# 36.net
KiCad netlist of a schematic drawn in Altium Designer
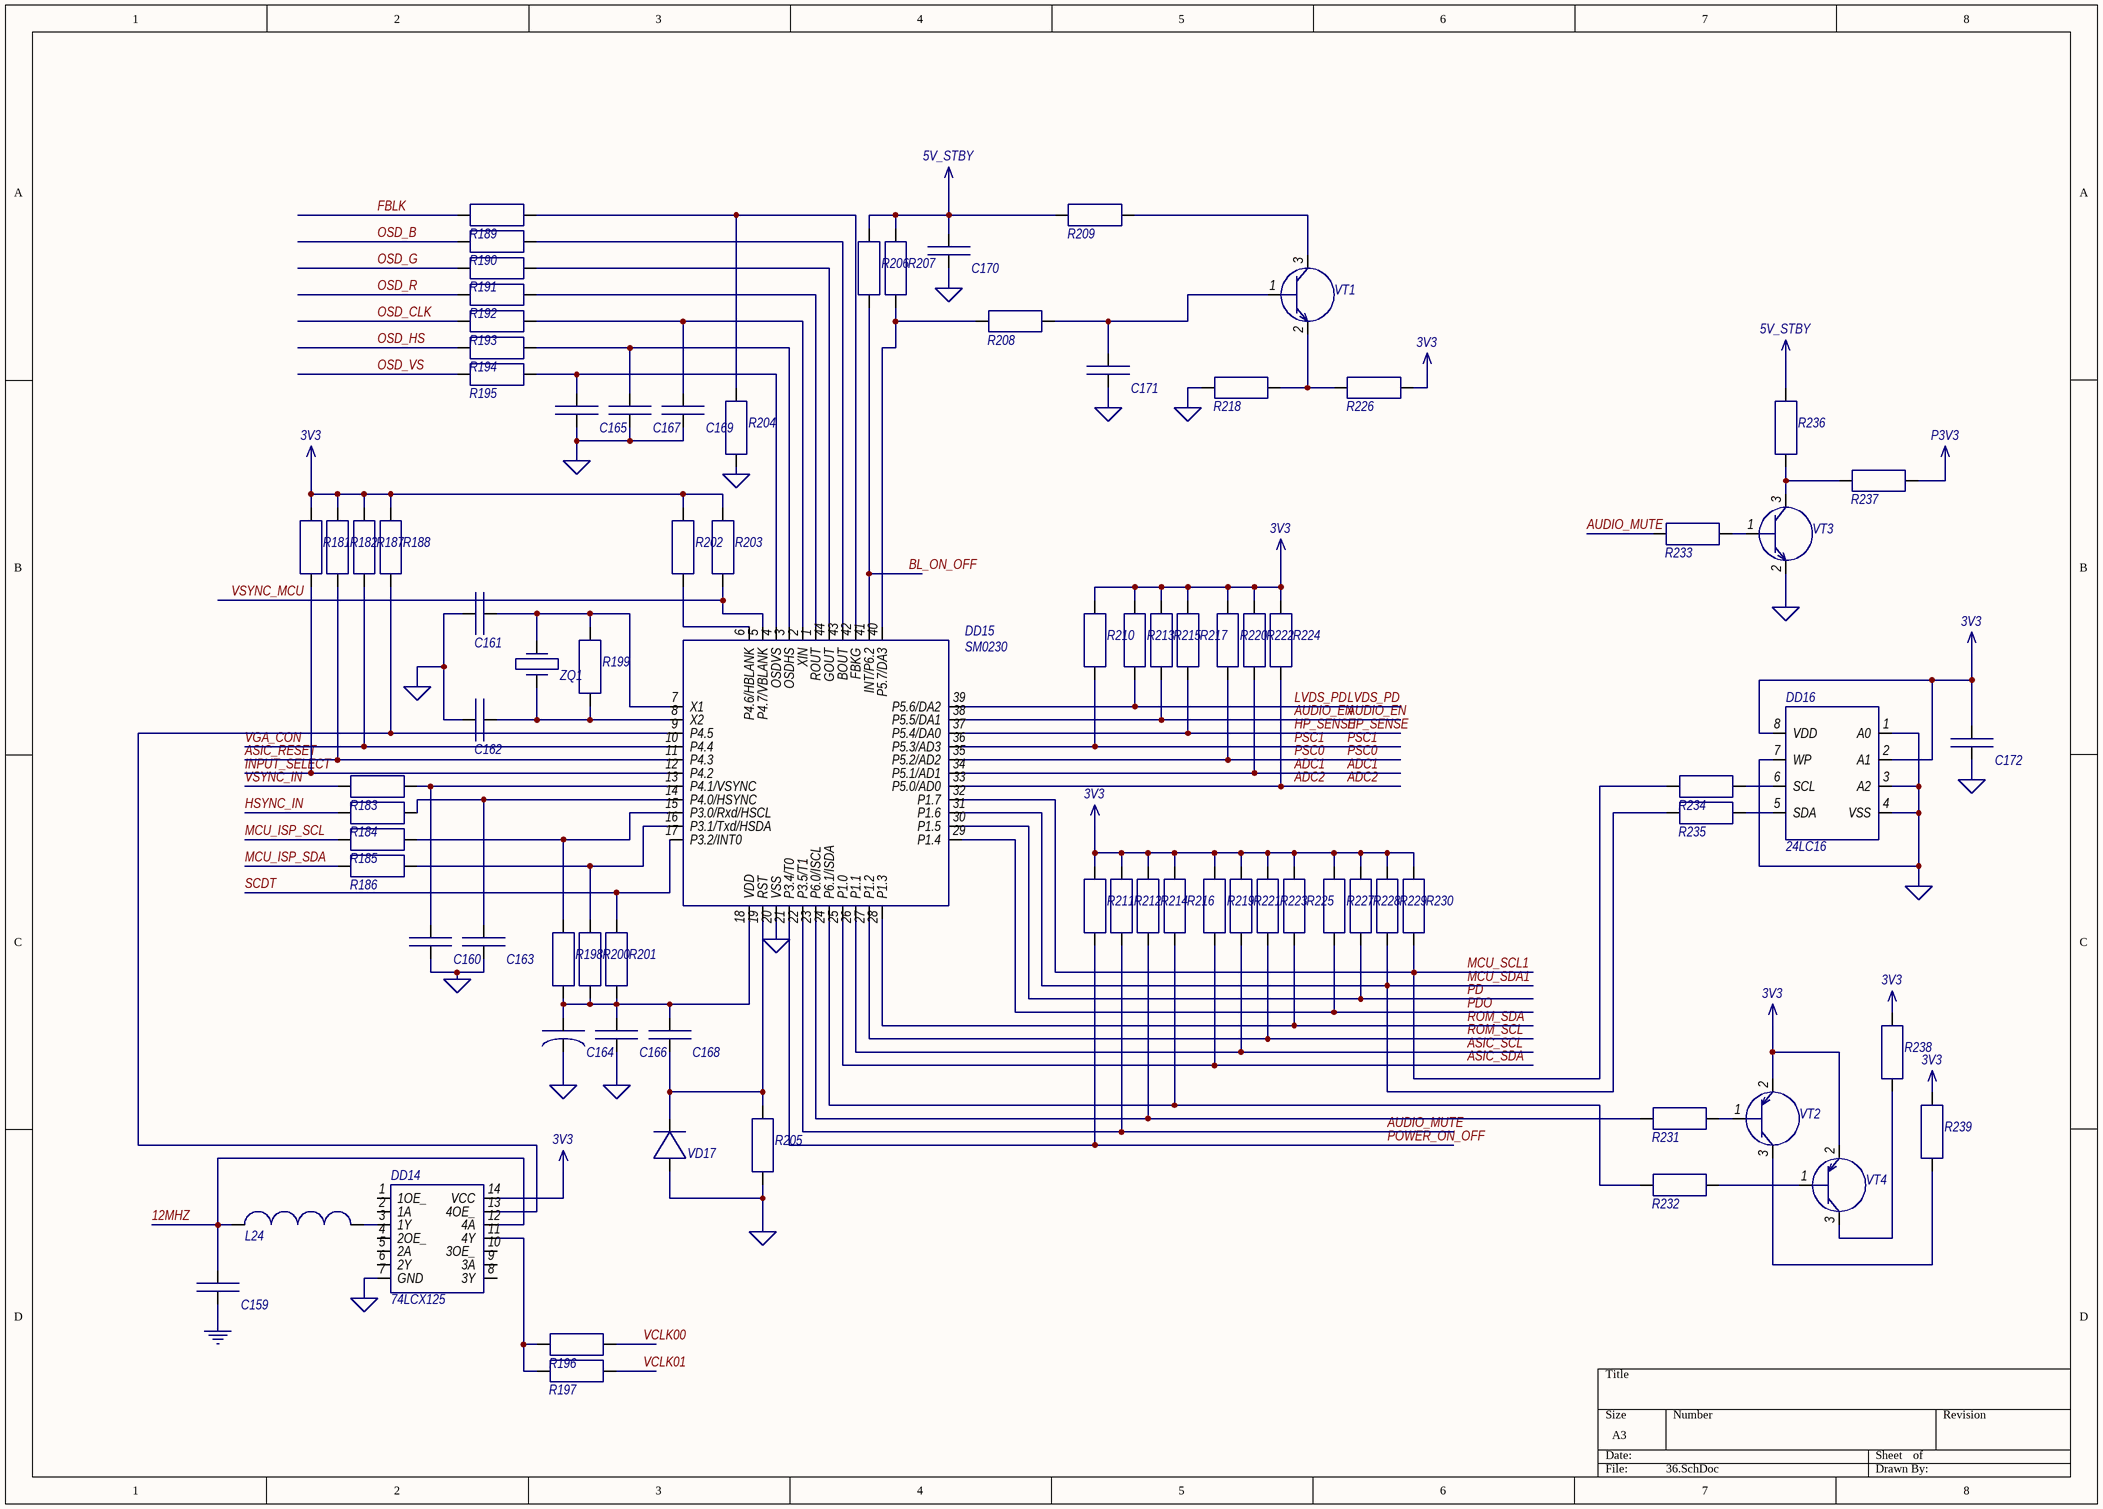
[diagram p0: 36.SchDoc]

(export (version "E")
  (design (tool "Eeschema 10.0.6"))
  (components
    (comp (ref "C159")
      (value "Capacitor")
      (footprint "cap_electro_13")
      (libsource (lib "31_lib") (part "Capacitor"))
    )
    (comp (ref "C160")
      (value "Capacitor")
      (footprint "cap_electro_13")
      (libsource (lib "31_lib") (part "Capacitor"))
    )
    (comp (ref "C161")
      (value "Capacitor")
      (footprint "cap_electro_13")
      (libsource (lib "31_lib") (part "Capacitor"))
    )
    (comp (ref "C162")
      (value "Capacitor")
      (footprint "cap_electro_13")
      (libsource (lib "31_lib") (part "Capacitor"))
    )
    (comp (ref "C163")
      (value "Capacitor")
      (footprint "cap_electro_13")
      (libsource (lib "31_lib") (part "Capacitor"))
    )
    (comp (ref "C164")
      (value "TuningCapacitor")
      (footprint "31_lib:Cap_tantal_D")
      (libsource (lib "31_lib") (part "TuningCapacitor"))
    )
    (comp (ref "C165")
      (value "Capacitor")
      (footprint "cap_electro_13")
      (libsource (lib "31_lib") (part "Capacitor"))
    )
    (comp (ref "C166")
      (value "Capacitor")
      (footprint "cap_electro_13")
      (libsource (lib "31_lib") (part "Capacitor"))
    )
    (comp (ref "C167")
      (value "Capacitor")
      (footprint "cap_electro_13")
      (libsource (lib "31_lib") (part "Capacitor"))
    )
    (comp (ref "C168")
      (value "Capacitor")
      (footprint "cap_electro_13")
      (libsource (lib "31_lib") (part "Capacitor"))
    )
    (comp (ref "C169")
      (value "Capacitor")
      (footprint "cap_electro_13")
      (libsource (lib "31_lib") (part "Capacitor"))
    )
    (comp (ref "C170")
      (value "Capacitor")
      (footprint "cap_electro_13")
      (libsource (lib "31_lib") (part "Capacitor"))
    )
    (comp (ref "C171")
      (value "Capacitor")
      (footprint "cap_electro_13")
      (libsource (lib "31_lib") (part "Capacitor"))
    )
    (comp (ref "C172")
      (value "Capacitor")
      (footprint "cap_electro_13")
      (libsource (lib "31_lib") (part "Capacitor"))
    )
    (comp (ref "DD14")
      (value "74LCX125")
      (footprint "31_lib:74LCX125(page12)")
      (libsource (lib "31_lib") (part "74LCX125"))
    )
    (comp (ref "DD15")
      (value "SM0230")
      (footprint "31_lib:SM0230")
      (libsource (lib "31_lib") (part "SM0230"))
    )
    (comp (ref "DD16") (value "24LC16") (footprint "31_lib:24Cxx") (libsource (lib "31_lib") (part "24LC16")))
    (comp (ref "L24")
      (value "Inductor")
      (footprint "31_lib:inductor")
      (libsource (lib "31_lib") (part "Inductor"))
    )
    (comp (ref "R181")
      (value "Resistor")
      (footprint "lab_7_footprints:R_1206")
      (libsource (lib "31_lib") (part "Resistor"))
    )
    (comp (ref "R182")
      (value "Resistor")
      (footprint "lab_7_footprints:R_1206")
      (libsource (lib "31_lib") (part "Resistor"))
    )
    (comp (ref "R183")
      (value "Resistor")
      (footprint "lab_7_footprints:R_1206")
      (libsource (lib "31_lib") (part "Resistor"))
    )
    (comp (ref "R184")
      (value "Resistor")
      (footprint "lab_7_footprints:R_1206")
      (libsource (lib "31_lib") (part "Resistor"))
    )
    (comp (ref "R185")
      (value "Resistor")
      (footprint "lab_7_footprints:R_1206")
      (libsource (lib "31_lib") (part "Resistor"))
    )
    (comp (ref "R186")
      (value "Resistor")
      (footprint "lab_7_footprints:R_1206")
      (libsource (lib "31_lib") (part "Resistor"))
    )
    (comp (ref "R187")
      (value "Resistor")
      (footprint "lab_7_footprints:R_1206")
      (libsource (lib "31_lib") (part "Resistor"))
    )
    (comp (ref "R188")
      (value "Resistor")
      (footprint "lab_7_footprints:R_1206")
      (libsource (lib "31_lib") (part "Resistor"))
    )
    (comp (ref "R189")
      (value "Resistor")
      (footprint "lab_7_footprints:R_1206")
      (libsource (lib "31_lib") (part "Resistor"))
    )
    (comp (ref "R190")
      (value "Resistor")
      (footprint "lab_7_footprints:R_1206")
      (libsource (lib "31_lib") (part "Resistor"))
    )
    (comp (ref "R191")
      (value "Resistor")
      (footprint "lab_7_footprints:R_1206")
      (libsource (lib "31_lib") (part "Resistor"))
    )
    (comp (ref "R192")
      (value "Resistor")
      (footprint "lab_7_footprints:R_1206")
      (libsource (lib "31_lib") (part "Resistor"))
    )
    (comp (ref "R193")
      (value "Resistor")
      (footprint "lab_7_footprints:R_1206")
      (libsource (lib "31_lib") (part "Resistor"))
    )
    (comp (ref "R194")
      (value "Resistor")
      (footprint "lab_7_footprints:R_1206")
      (libsource (lib "31_lib") (part "Resistor"))
    )
    (comp (ref "R195")
      (value "Resistor")
      (footprint "lab_7_footprints:R_1206")
      (libsource (lib "31_lib") (part "Resistor"))
    )
    (comp (ref "R196")
      (value "Resistor")
      (footprint "lab_7_footprints:R_1206")
      (libsource (lib "31_lib") (part "Resistor"))
    )
    (comp (ref "R197")
      (value "Resistor")
      (footprint "lab_7_footprints:R_1206")
      (libsource (lib "31_lib") (part "Resistor"))
    )
    (comp (ref "R198")
      (value "Resistor")
      (footprint "lab_7_footprints:R_1206")
      (libsource (lib "31_lib") (part "Resistor"))
    )
    (comp (ref "R199")
      (value "Resistor")
      (footprint "lab_7_footprints:R_1206")
      (libsource (lib "31_lib") (part "Resistor"))
    )
    (comp (ref "R200")
      (value "Resistor")
      (footprint "lab_7_footprints:R_1206")
      (libsource (lib "31_lib") (part "Resistor"))
    )
    (comp (ref "R201")
      (value "Resistor")
      (footprint "lab_7_footprints:R_1206")
      (libsource (lib "31_lib") (part "Resistor"))
    )
    (comp (ref "R202")
      (value "Resistor")
      (footprint "lab_7_footprints:R_1206")
      (libsource (lib "31_lib") (part "Resistor"))
    )
    (comp (ref "R203")
      (value "Resistor")
      (footprint "lab_7_footprints:R_1206")
      (libsource (lib "31_lib") (part "Resistor"))
    )
    (comp (ref "R204")
      (value "Resistor")
      (footprint "lab_7_footprints:R_1206")
      (libsource (lib "31_lib") (part "Resistor"))
    )
    (comp (ref "R205")
      (value "Resistor")
      (footprint "lab_7_footprints:R_1206")
      (libsource (lib "31_lib") (part "Resistor"))
    )
    (comp (ref "R206")
      (value "Resistor")
      (footprint "lab_7_footprints:R_1206")
      (libsource (lib "31_lib") (part "Resistor"))
    )
    (comp (ref "R207")
      (value "Resistor")
      (footprint "lab_7_footprints:R_1206")
      (libsource (lib "31_lib") (part "Resistor"))
    )
    (comp (ref "R208")
      (value "Resistor")
      (footprint "lab_7_footprints:R_1206")
      (libsource (lib "31_lib") (part "Resistor"))
    )
    (comp (ref "R209")
      (value "Resistor")
      (footprint "lab_7_footprints:R_1206")
      (libsource (lib "31_lib") (part "Resistor"))
    )
    (comp (ref "R210")
      (value "Resistor")
      (footprint "lab_7_footprints:R_1206")
      (libsource (lib "31_lib") (part "Resistor"))
    )
    (comp (ref "R211")
      (value "Resistor")
      (footprint "lab_7_footprints:R_1206")
      (libsource (lib "31_lib") (part "Resistor"))
    )
    (comp (ref "R212")
      (value "Resistor")
      (footprint "lab_7_footprints:R_1206")
      (libsource (lib "31_lib") (part "Resistor"))
    )
    (comp (ref "R213")
      (value "Resistor")
      (footprint "lab_7_footprints:R_1206")
      (libsource (lib "31_lib") (part "Resistor"))
    )
    (comp (ref "R214")
      (value "Resistor")
      (footprint "lab_7_footprints:R_1206")
      (libsource (lib "31_lib") (part "Resistor"))
    )
    (comp (ref "R215")
      (value "Resistor")
      (footprint "lab_7_footprints:R_1206")
      (libsource (lib "31_lib") (part "Resistor"))
    )
    (comp (ref "R216")
      (value "Resistor")
      (footprint "lab_7_footprints:R_1206")
      (libsource (lib "31_lib") (part "Resistor"))
    )
    (comp (ref "R217")
      (value "Resistor")
      (footprint "lab_7_footprints:R_1206")
      (libsource (lib "31_lib") (part "Resistor"))
    )
    (comp (ref "R218")
      (value "Resistor")
      (footprint "lab_7_footprints:R_1206")
      (libsource (lib "31_lib") (part "Resistor"))
    )
    (comp (ref "R219")
      (value "Resistor")
      (footprint "lab_7_footprints:R_1206")
      (libsource (lib "31_lib") (part "Resistor"))
    )
    (comp (ref "R220")
      (value "Resistor")
      (footprint "lab_7_footprints:R_1206")
      (libsource (lib "31_lib") (part "Resistor"))
    )
    (comp (ref "R221")
      (value "Resistor")
      (footprint "lab_7_footprints:R_1206")
      (libsource (lib "31_lib") (part "Resistor"))
    )
    (comp (ref "R222")
      (value "Resistor")
      (footprint "lab_7_footprints:R_1206")
      (libsource (lib "31_lib") (part "Resistor"))
    )
    (comp (ref "R223")
      (value "Resistor")
      (footprint "lab_7_footprints:R_1206")
      (libsource (lib "31_lib") (part "Resistor"))
    )
    (comp (ref "R224")
      (value "Resistor")
      (footprint "lab_7_footprints:R_1206")
      (libsource (lib "31_lib") (part "Resistor"))
    )
    (comp (ref "R225")
      (value "Resistor")
      (footprint "lab_7_footprints:R_1206")
      (libsource (lib "31_lib") (part "Resistor"))
    )
    (comp (ref "R226")
      (value "Resistor")
      (footprint "lab_7_footprints:R_1206")
      (libsource (lib "31_lib") (part "Resistor"))
    )
    (comp (ref "R227")
      (value "Resistor")
      (footprint "lab_7_footprints:R_1206")
      (libsource (lib "31_lib") (part "Resistor"))
    )
    (comp (ref "R228")
      (value "Resistor")
      (footprint "lab_7_footprints:R_1206")
      (libsource (lib "31_lib") (part "Resistor"))
    )
    (comp (ref "R229")
      (value "Resistor")
      (footprint "lab_7_footprints:R_1206")
      (libsource (lib "31_lib") (part "Resistor"))
    )
    (comp (ref "R230")
      (value "Resistor")
      (footprint "lab_7_footprints:R_1206")
      (libsource (lib "31_lib") (part "Resistor"))
    )
    (comp (ref "R231")
      (value "Resistor")
      (footprint "lab_7_footprints:R_1206")
      (libsource (lib "31_lib") (part "Resistor"))
    )
    (comp (ref "R232")
      (value "Resistor")
      (footprint "lab_7_footprints:R_1206")
      (libsource (lib "31_lib") (part "Resistor"))
    )
    (comp (ref "R233")
      (value "Resistor")
      (footprint "lab_7_footprints:R_1206")
      (libsource (lib "31_lib") (part "Resistor"))
    )
    (comp (ref "R234")
      (value "Resistor")
      (footprint "lab_7_footprints:R_1206")
      (libsource (lib "31_lib") (part "Resistor"))
    )
    (comp (ref "R235")
      (value "Resistor")
      (footprint "lab_7_footprints:R_1206")
      (libsource (lib "31_lib") (part "Resistor"))
    )
    (comp (ref "R236")
      (value "Resistor")
      (footprint "lab_7_footprints:R_1206")
      (libsource (lib "31_lib") (part "Resistor"))
    )
    (comp (ref "R237")
      (value "Resistor")
      (footprint "lab_7_footprints:R_1206")
      (libsource (lib "31_lib") (part "Resistor"))
    )
    (comp (ref "R238")
      (value "Resistor")
      (footprint "lab_7_footprints:R_1206")
      (libsource (lib "31_lib") (part "Resistor"))
    )
    (comp (ref "R239")
      (value "Resistor")
      (footprint "lab_7_footprints:R_1206")
      (libsource (lib "31_lib") (part "Resistor"))
    )
    (comp (ref "VD17")
      (value "Diode")
      (footprint "lab_7_footprints:zener_diode")
      (libsource (lib "31_lib") (part "Diode"))
    )
    (comp (ref "VT1")
      (value "MMBT3904L")
      (footprint "31_lib:MMBT3904L")
      (libsource (lib "31_lib") (part "MMBT3904L"))
    )
    (comp (ref "VT2") (value "2N3906") (footprint "31_lib:2N3906") (libsource (lib "31_lib") (part "2N3906")))
    (comp (ref "VT3")
      (value "MMBT3904L")
      (footprint "31_lib:MMBT3904L")
      (libsource (lib "31_lib") (part "MMBT3904L"))
    )
    (comp (ref "VT4") (value "2N3906") (footprint "31_lib:2N3906") (libsource (lib "31_lib") (part "2N3906")))
    (comp (ref "ZQ1")
      (value "Crystal")
      (footprint "lab_7_footprints:crystal")
      (libsource (lib "31_lib") (part "Crystal"))
    )
  )
  (nets
    (net (code "1") (name "/12MHZ") (class "Default")
      (node (ref "C159") (pin "1") (pinfunction "1_1") (pintype "passive"))
      (node (ref "DD14") (pin "12") (pinfunction "4A_12") (pintype "passive"))
      (node (ref "L24") (pin "1") (pinfunction "1_1") (pintype "passive"))
    )
    (net (code "2") (name "/ADC1") (class "Default")
      (node (ref "DD15") (pin "34") (pinfunction "P5.1/AD1_34") (pintype "passive"))
      (node (ref "R222") (pin "2") (pinfunction "2_2") (pintype "passive"))
    )
    (net (code "3") (name "/ADC2") (class "Default")
      (node (ref "DD15") (pin "33") (pinfunction "P5.0/AD0_33") (pintype "passive"))
      (node (ref "R224") (pin "2") (pinfunction "2_2") (pintype "passive"))
    )
    (net (code "4") (name "/ASIC_RESET") (class "Default")
      (node (ref "DD15") (pin "11") (pinfunction "P4.3_11") (pintype "passive"))
      (node (ref "R182") (pin "1") (pinfunction "1_1") (pintype "passive"))
    )
    (net (code "5") (name "/ASIC_SCL") (class "Default")
      (node (ref "DD15") (pin "26") (pinfunction "P1.1_26") (pintype "passive"))
      (node (ref "R221") (pin "2") (pinfunction "2_2") (pintype "passive"))
    )
    (net (code "6") (name "/ASIC_SDA") (class "Default")
      (node (ref "DD15") (pin "25") (pinfunction "P1.0_25") (pintype "passive"))
      (node (ref "R219") (pin "2") (pinfunction "2_2") (pintype "passive"))
    )
    (net (code "7") (name "/AUDIO_EN") (class "Default")
      (node (ref "DD15") (pin "38") (pinfunction "P5.5/DA1_38") (pintype "passive"))
      (node (ref "R215") (pin "2") (pinfunction "2_2") (pintype "passive"))
    )
    (net (code "8") (name "/AUDIO_MUTE") (class "Default")
      (node (ref "DD15") (pin "22") (pinfunction "P3.5/T1_22") (pintype "passive"))
      (node (ref "R212") (pin "2") (pinfunction "2_2") (pintype "passive"))
      (node (ref "R233") (pin "1") (pinfunction "1_1") (pintype "passive"))
    )
    (net (code "9") (name "/BL_ON_OFF") (class "Default")
      (node (ref "DD15") (pin "41") (pinfunction "INT/P6.2_41") (pintype "passive"))
      (node (ref "R206") (pin "2") (pinfunction "2_2") (pintype "passive"))
    )
    (net (code "10") (name "/FBLK") (class "Default")
      (node (ref "R189") (pin "2") (pinfunction "2_2") (pintype "passive"))
    )
    (net (code "11") (name "/HP_SENSE") (class "Default")
      (node (ref "DD15") (pin "37") (pinfunction "P5.4/DA0_37") (pintype "passive"))
      (node (ref "R217") (pin "2") (pinfunction "2_2") (pintype "passive"))
    )
    (net (code "12") (name "/HSYNC_IN") (class "Default")
      (node (ref "R184") (pin "1") (pinfunction "1_1") (pintype "passive"))
    )
    (net (code "13") (name "/INPUT_SELECT") (class "Default")
      (node (ref "DD15") (pin "12") (pinfunction "P4.2_12") (pintype "passive"))
      (node (ref "R181") (pin "1") (pinfunction "1_1") (pintype "passive"))
    )
    (net (code "14") (name "/LVDS_PD") (class "Default")
      (node (ref "DD15") (pin "39") (pinfunction "P5.6/DA2_39") (pintype "passive"))
      (node (ref "R213") (pin "2") (pinfunction "2_2") (pintype "passive"))
    )
    (net (code "15") (name "/MCU_ISP_SCL") (class "Default")
      (node (ref "R185") (pin "1") (pinfunction "1_1") (pintype "passive"))
    )
    (net (code "16") (name "/MCU_ISP_SDA") (class "Default")
      (node (ref "R186") (pin "1") (pinfunction "1_1") (pintype "passive"))
    )
    (net (code "17") (name "/MCU_SCL1") (class "Default")
      (node (ref "DD15") (pin "32") (pinfunction "P1.7_32") (pintype "passive"))
      (node (ref "R230") (pin "2") (pinfunction "2_2") (pintype "passive"))
      (node (ref "R234") (pin "1") (pinfunction "1_1") (pintype "passive"))
    )
    (net (code "18") (name "/MCU_SDA1") (class "Default")
      (node (ref "DD15") (pin "31") (pinfunction "P1.6_31") (pintype "passive"))
      (node (ref "R229") (pin "2") (pinfunction "2_2") (pintype "passive"))
      (node (ref "R235") (pin "1") (pinfunction "1_1") (pintype "passive"))
    )
    (net (code "19") (name "/OSD_B") (class "Default")
      (node (ref "R190") (pin "2") (pinfunction "2_2") (pintype "passive"))
    )
    (net (code "20") (name "/OSD_CLK") (class "Default")
      (node (ref "R193") (pin "2") (pinfunction "2_2") (pintype "passive"))
    )
    (net (code "21") (name "/OSD_G") (class "Default")
      (node (ref "R191") (pin "2") (pinfunction "2_2") (pintype "passive"))
    )
    (net (code "22") (name "/OSD_HS") (class "Default")
      (node (ref "R194") (pin "2") (pinfunction "2_2") (pintype "passive"))
    )
    (net (code "23") (name "/OSD_R") (class "Default")
      (node (ref "R192") (pin "2") (pinfunction "2_2") (pintype "passive"))
    )
    (net (code "24") (name "/OSD_VS") (class "Default")
      (node (ref "R195") (pin "2") (pinfunction "2_2") (pintype "passive"))
    )
    (net (code "25") (name "/PD") (class "Default")
      (node (ref "DD15") (pin "30") (pinfunction "P1.5_30") (pintype "passive"))
      (node (ref "R228") (pin "2") (pinfunction "2_2") (pintype "passive"))
    )
    (net (code "26") (name "/PDO") (class "Default")
      (node (ref "DD15") (pin "29") (pinfunction "P1.4_29") (pintype "passive"))
      (node (ref "R227") (pin "2") (pinfunction "2_2") (pintype "passive"))
    )
    (net (code "27") (name "/POWER_ON_OFF") (class "Default")
      (node (ref "DD15") (pin "21") (pinfunction "P3.4/T0_21") (pintype "passive"))
      (node (ref "R211") (pin "2") (pinfunction "2_2") (pintype "passive"))
    )
    (net (code "28") (name "/PSC0") (class "Default")
      (node (ref "DD15") (pin "35") (pinfunction "P5.2/AD2_35") (pintype "passive"))
      (node (ref "R220") (pin "2") (pinfunction "2_2") (pintype "passive"))
    )
    (net (code "29") (name "/PSC1") (class "Default")
      (node (ref "DD15") (pin "36") (pinfunction "P5.3/AD3_36") (pintype "passive"))
      (node (ref "R210") (pin "2") (pinfunction "2_2") (pintype "passive"))
    )
    (net (code "30") (name "/ROM_SCL") (class "Default")
      (node (ref "DD15") (pin "27") (pinfunction "P1.2_27") (pintype "passive"))
      (node (ref "R223") (pin "2") (pinfunction "2_2") (pintype "passive"))
    )
    (net (code "31") (name "/ROM_SDA") (class "Default")
      (node (ref "DD15") (pin "28") (pinfunction "P1.3_28") (pintype "passive"))
      (node (ref "R225") (pin "2") (pinfunction "2_2") (pintype "passive"))
    )
    (net (code "32") (name "/SCDT") (class "Default")
      (node (ref "DD15") (pin "17") (pinfunction "P3.2/INT0_17") (pintype "passive"))
      (node (ref "R201") (pin "2") (pinfunction "2_2") (pintype "passive"))
    )
    (net (code "33") (name "/VCLK00") (class "Default")
      (node (ref "R196") (pin "2") (pinfunction "2_2") (pintype "passive"))
    )
    (net (code "34") (name "/VCLK01") (class "Default")
      (node (ref "R197") (pin "2") (pinfunction "2_2") (pintype "passive"))
    )
    (net (code "35") (name "/VGA_CON") (class "Default")
      (node (ref "DD15") (pin "10") (pinfunction "P4.4_10") (pintype "passive"))
      (node (ref "R187") (pin "1") (pinfunction "1_1") (pintype "passive"))
    )
    (net (code "36") (name "/VSYNC_IN") (class "Default")
      (node (ref "R183") (pin "1") (pinfunction "1_1") (pintype "passive"))
    )
    (net (code "37") (name "/VSYNC_MCU") (class "Default")
      (node (ref "DD15") (pin "5") (pinfunction "P4.7/VBLANK_5") (pintype "passive"))
      (node (ref "R203") (pin "1") (pinfunction "1_1") (pintype "passive"))
    )
    (net (code "38") (name "3V3") (class "Default")
      (node (ref "C172") (pin "1") (pinfunction "1_1") (pintype "passive"))
      (node (ref "DD14") (pin "14") (pinfunction "VCC_14") (pintype "passive"))
      (node (ref "DD16") (pin "2") (pinfunction "A1_2") (pintype "passive"))
      (node (ref "DD16") (pin "8") (pinfunction "VDD_8") (pintype "passive"))
      (node (ref "R181") (pin "2") (pinfunction "2_2") (pintype "passive"))
      (node (ref "R182") (pin "2") (pinfunction "2_2") (pintype "passive"))
      (node (ref "R187") (pin "2") (pinfunction "2_2") (pintype "passive"))
      (node (ref "R188") (pin "2") (pinfunction "2_2") (pintype "passive"))
      (node (ref "R202") (pin "2") (pinfunction "2_2") (pintype "passive"))
      (node (ref "R203") (pin "2") (pinfunction "2_2") (pintype "passive"))
      (node (ref "R210") (pin "1") (pinfunction "1_1") (pintype "passive"))
      (node (ref "R211") (pin "1") (pinfunction "1_1") (pintype "passive"))
      (node (ref "R212") (pin "1") (pinfunction "1_1") (pintype "passive"))
      (node (ref "R213") (pin "1") (pinfunction "1_1") (pintype "passive"))
      (node (ref "R214") (pin "1") (pinfunction "1_1") (pintype "passive"))
      (node (ref "R215") (pin "1") (pinfunction "1_1") (pintype "passive"))
      (node (ref "R216") (pin "1") (pinfunction "1_1") (pintype "passive"))
      (node (ref "R217") (pin "1") (pinfunction "1_1") (pintype "passive"))
      (node (ref "R219") (pin "1") (pinfunction "1_1") (pintype "passive"))
      (node (ref "R220") (pin "1") (pinfunction "1_1") (pintype "passive"))
      (node (ref "R221") (pin "1") (pinfunction "1_1") (pintype "passive"))
      (node (ref "R222") (pin "1") (pinfunction "1_1") (pintype "passive"))
      (node (ref "R223") (pin "1") (pinfunction "1_1") (pintype "passive"))
      (node (ref "R224") (pin "1") (pinfunction "1_1") (pintype "passive"))
      (node (ref "R225") (pin "1") (pinfunction "1_1") (pintype "passive"))
      (node (ref "R226") (pin "2") (pinfunction "2_2") (pintype "passive"))
      (node (ref "R227") (pin "1") (pinfunction "1_1") (pintype "passive"))
      (node (ref "R228") (pin "1") (pinfunction "1_1") (pintype "passive"))
      (node (ref "R229") (pin "1") (pinfunction "1_1") (pintype "passive"))
      (node (ref "R230") (pin "1") (pinfunction "1_1") (pintype "passive"))
      (node (ref "R238") (pin "2") (pinfunction "2_2") (pintype "passive"))
      (node (ref "R239") (pin "2") (pinfunction "2_2") (pintype "passive"))
      (node (ref "VT2") (pin "2") (pinfunction "Emitter_2") (pintype "passive"))
      (node (ref "VT4") (pin "2") (pinfunction "Emitter_2") (pintype "passive"))
    )
    (net (code "39") (name "5V_STBY") (class "Default")
      (node (ref "C170") (pin "1") (pinfunction "1_1") (pintype "passive"))
      (node (ref "R206") (pin "1") (pinfunction "1_1") (pintype "passive"))
      (node (ref "R207") (pin "1") (pinfunction "1_1") (pintype "passive"))
      (node (ref "R209") (pin "1") (pinfunction "1_1") (pintype "passive"))
      (node (ref "R236") (pin "2") (pinfunction "2_2") (pintype "passive"))
    )
    (net (code "40") (name "GND") (class "Default")
      (node (ref "C159") (pin "2") (pinfunction "2_2") (pintype "passive"))
      (node (ref "C160") (pin "1") (pinfunction "1_1") (pintype "passive"))
      (node (ref "C161") (pin "2") (pinfunction "2_2") (pintype "passive"))
      (node (ref "C162") (pin "2") (pinfunction "2_2") (pintype "passive"))
      (node (ref "C163") (pin "1") (pinfunction "1_1") (pintype "passive"))
      (node (ref "C164") (pin "2") (pinfunction "2_2") (pintype "passive"))
      (node (ref "C165") (pin "2") (pinfunction "2_2") (pintype "passive"))
      (node (ref "C166") (pin "1") (pinfunction "1_1") (pintype "passive"))
      (node (ref "C167") (pin "2") (pinfunction "2_2") (pintype "passive"))
      (node (ref "C169") (pin "2") (pinfunction "2_2") (pintype "passive"))
      (node (ref "C170") (pin "2") (pinfunction "2_2") (pintype "passive"))
      (node (ref "C171") (pin "2") (pinfunction "2_2") (pintype "passive"))
      (node (ref "C172") (pin "2") (pinfunction "2_2") (pintype "passive"))
      (node (ref "DD14") (pin "7") (pinfunction "GND_7") (pintype "passive"))
      (node (ref "DD15") (pin "20") (pinfunction "VSS_20") (pintype "passive"))
      (node (ref "DD16") (pin "1") (pinfunction "A0_1") (pintype "passive"))
      (node (ref "DD16") (pin "3") (pinfunction "A2_3") (pintype "passive"))
      (node (ref "DD16") (pin "4") (pinfunction "VSS_4") (pintype "passive"))
      (node (ref "DD16") (pin "7") (pinfunction "WP_7") (pintype "passive"))
      (node (ref "R204") (pin "1") (pinfunction "1_1") (pintype "passive"))
      (node (ref "R205") (pin "1") (pinfunction "1_1") (pintype "passive"))
      (node (ref "R218") (pin "1") (pinfunction "1_1") (pintype "passive"))
      (node (ref "VD17") (pin "1") (pinfunction "1_1") (pintype "passive"))
      (node (ref "VT3") (pin "2") (pinfunction "Emitter_2") (pintype "passive"))
    )
    (net (code "41") (name "Net-(DD14-1Y)") (class "Default")
      (node (ref "DD14") (pin "3") (pinfunction "1Y_3") (pintype "passive"))
      (node (ref "L24") (pin "2") (pinfunction "2_2") (pintype "passive"))
    )
    (net (code "42") (name "Net-(DD14-4OE_)") (class "Default")
      (node (ref "DD14") (pin "13") (pinfunction "4OE__13") (pintype "passive"))
      (node (ref "DD15") (pin "9") (pinfunction "P4.5_9") (pintype "passive"))
      (node (ref "R188") (pin "1") (pinfunction "1_1") (pintype "passive"))
    )
    (net (code "43") (name "Net-(DD14-4Y)") (class "Default")
      (node (ref "DD14") (pin "11") (pinfunction "4Y_11") (pintype "passive"))
      (node (ref "R196") (pin "1") (pinfunction "1_1") (pintype "passive"))
      (node (ref "R197") (pin "1") (pinfunction "1_1") (pintype "passive"))
    )
    (net (code "44") (name "Net-(DD15-BOUT)") (class "Default")
      (node (ref "DD15") (pin "43") (pinfunction "BOUT_43") (pintype "passive"))
      (node (ref "R190") (pin "1") (pinfunction "1_1") (pintype "passive"))
    )
    (net (code "45") (name "Net-(DD15-FBKG)") (class "Default")
      (node (ref "DD15") (pin "42") (pinfunction "FBKG_42") (pintype "passive"))
      (node (ref "R189") (pin "1") (pinfunction "1_1") (pintype "passive"))
      (node (ref "R204") (pin "2") (pinfunction "2_2") (pintype "passive"))
    )
    (net (code "46") (name "Net-(DD15-GOUT)") (class "Default")
      (node (ref "DD15") (pin "44") (pinfunction "GOUT_44") (pintype "passive"))
      (node (ref "R191") (pin "1") (pinfunction "1_1") (pintype "passive"))
    )
    (net (code "47") (name "Net-(DD15-OSDHS)") (class "Default")
      (node (ref "C167") (pin "1") (pinfunction "1_1") (pintype "passive"))
      (node (ref "DD15") (pin "3") (pinfunction "OSDHS_3") (pintype "passive"))
      (node (ref "R194") (pin "1") (pinfunction "1_1") (pintype "passive"))
    )
    (net (code "48") (name "Net-(DD15-OSDVS)") (class "Default")
      (node (ref "C165") (pin "1") (pinfunction "1_1") (pintype "passive"))
      (node (ref "DD15") (pin "4") (pinfunction "OSDVS_4") (pintype "passive"))
      (node (ref "R195") (pin "1") (pinfunction "1_1") (pintype "passive"))
    )
    (net (code "49") (name "Net-(DD15-P3.0{slash}Rxd{slash}HSCL)") (class "Default")
      (node (ref "DD15") (pin "15") (pinfunction "P3.0/Rxd/HSCL_15") (pintype "passive"))
      (node (ref "R185") (pin "2") (pinfunction "2_2") (pintype "passive"))
      (node (ref "R198") (pin "2") (pinfunction "2_2") (pintype "passive"))
    )
    (net (code "50") (name "Net-(DD15-P3.1{slash}Txd{slash}HSDA)") (class "Default")
      (node (ref "DD15") (pin "16") (pinfunction "P3.1/Txd/HSDA_16") (pintype "passive"))
      (node (ref "R186") (pin "2") (pinfunction "2_2") (pintype "passive"))
      (node (ref "R200") (pin "2") (pinfunction "2_2") (pintype "passive"))
    )
    (net (code "51") (name "Net-(DD15-P4.0{slash}HSYNC)") (class "Default")
      (node (ref "C163") (pin "2") (pinfunction "2_2") (pintype "passive"))
      (node (ref "DD15") (pin "14") (pinfunction "P4.0/HSYNC_14") (pintype "passive"))
      (node (ref "R184") (pin "2") (pinfunction "2_2") (pintype "passive"))
    )
    (net (code "52") (name "Net-(DD15-P4.1{slash}VSYNC)") (class "Default")
      (node (ref "C160") (pin "2") (pinfunction "2_2") (pintype "passive"))
      (node (ref "DD15") (pin "13") (pinfunction "P4.1/VSYNC_13") (pintype "passive"))
      (node (ref "R183") (pin "2") (pinfunction "2_2") (pintype "passive"))
    )
    (net (code "53") (name "Net-(DD15-P4.6{slash}HBLANK)") (class "Default")
      (node (ref "DD15") (pin "6") (pinfunction "P4.6/HBLANK_6") (pintype "passive"))
      (node (ref "R202") (pin "1") (pinfunction "1_1") (pintype "passive"))
    )
    (net (code "54") (name "Net-(DD15-P5.7{slash}DA3)") (class "Default")
      (node (ref "DD15") (pin "40") (pinfunction "P5.7/DA3_40") (pintype "passive"))
      (node (ref "R207") (pin "2") (pinfunction "2_2") (pintype "passive"))
      (node (ref "R208") (pin "1") (pinfunction "1_1") (pintype "passive"))
    )
    (net (code "55") (name "Net-(DD15-P6.0{slash}ISCL)") (class "Default")
      (node (ref "DD15") (pin "23") (pinfunction "P6.0/ISCL_23") (pintype "passive"))
      (node (ref "R214") (pin "2") (pinfunction "2_2") (pintype "passive"))
      (node (ref "R231") (pin "1") (pinfunction "1_1") (pintype "passive"))
    )
    (net (code "56") (name "Net-(DD15-P6.1{slash}ISDA)") (class "Default")
      (node (ref "DD15") (pin "24") (pinfunction "P6.1/ISDA_24") (pintype "passive"))
      (node (ref "R216") (pin "2") (pinfunction "2_2") (pintype "passive"))
      (node (ref "R232") (pin "1") (pinfunction "1_1") (pintype "passive"))
    )
    (net (code "57") (name "Net-(DD15-ROUT)") (class "Default")
      (node (ref "DD15") (pin "1") (pinfunction "ROUT_1") (pintype "passive"))
      (node (ref "R192") (pin "1") (pinfunction "1_1") (pintype "passive"))
    )
    (net (code "58") (name "Net-(DD15-RST)") (class "Default")
      (node (ref "C168") (pin "1") (pinfunction "1_1") (pintype "passive"))
      (node (ref "DD15") (pin "19") (pinfunction "RST_19") (pintype "passive"))
      (node (ref "R205") (pin "2") (pinfunction "2_2") (pintype "passive"))
      (node (ref "VD17") (pin "2") (pinfunction "2_2") (pintype "passive"))
    )
    (net (code "59") (name "Net-(DD15-VDD)") (class "Default")
      (node (ref "C164") (pin "1") (pinfunction "1_1") (pintype "passive"))
      (node (ref "C166") (pin "2") (pinfunction "2_2") (pintype "passive"))
      (node (ref "C168") (pin "2") (pinfunction "2_2") (pintype "passive"))
      (node (ref "DD15") (pin "18") (pinfunction "VDD_18") (pintype "passive"))
      (node (ref "R198") (pin "1") (pinfunction "1_1") (pintype "passive"))
      (node (ref "R200") (pin "1") (pinfunction "1_1") (pintype "passive"))
      (node (ref "R201") (pin "1") (pinfunction "1_1") (pintype "passive"))
    )
    (net (code "60") (name "Net-(DD15-X1)") (class "Default")
      (node (ref "C161") (pin "1") (pinfunction "1_1") (pintype "passive"))
      (node (ref "DD15") (pin "7") (pinfunction "X1_7") (pintype "passive"))
      (node (ref "R199") (pin "2") (pinfunction "2_2") (pintype "passive"))
      (node (ref "ZQ1") (pin "2") (pinfunction "2_2") (pintype "passive"))
    )
    (net (code "61") (name "Net-(DD15-X2)") (class "Default")
      (node (ref "C162") (pin "1") (pinfunction "1_1") (pintype "passive"))
      (node (ref "DD15") (pin "8") (pinfunction "X2_8") (pintype "passive"))
      (node (ref "R199") (pin "1") (pinfunction "1_1") (pintype "passive"))
      (node (ref "ZQ1") (pin "1") (pinfunction "1_1") (pintype "passive"))
    )
    (net (code "62") (name "Net-(DD15-XIN)") (class "Default")
      (node (ref "C169") (pin "1") (pinfunction "1_1") (pintype "passive"))
      (node (ref "DD15") (pin "2") (pinfunction "XIN_2") (pintype "passive"))
      (node (ref "R193") (pin "1") (pinfunction "1_1") (pintype "passive"))
    )
    (net (code "63") (name "Net-(DD16-SCL)") (class "Default")
      (node (ref "DD16") (pin "6") (pinfunction "SCL_6") (pintype "passive"))
      (node (ref "R234") (pin "2") (pinfunction "2_2") (pintype "passive"))
    )
    (net (code "64") (name "Net-(DD16-SDA)") (class "Default")
      (node (ref "DD16") (pin "5") (pinfunction "SDA_5") (pintype "passive"))
      (node (ref "R235") (pin "2") (pinfunction "2_2") (pintype "passive"))
    )
    (net (code "65") (name "Net-(VT1-Base)") (class "Default")
      (node (ref "C171") (pin "1") (pinfunction "1_1") (pintype "passive"))
      (node (ref "R208") (pin "2") (pinfunction "2_2") (pintype "passive"))
      (node (ref "VT1") (pin "1") (pinfunction "Base_1") (pintype "passive"))
    )
    (net (code "66") (name "Net-(VT1-Collector)") (class "Default")
      (node (ref "R209") (pin "2") (pinfunction "2_2") (pintype "passive"))
      (node (ref "VT1") (pin "3") (pinfunction "Collector_3") (pintype "passive"))
    )
    (net (code "67") (name "Net-(VT1-Emitter)") (class "Default")
      (node (ref "R218") (pin "2") (pinfunction "2_2") (pintype "passive"))
      (node (ref "R226") (pin "1") (pinfunction "1_1") (pintype "passive"))
      (node (ref "VT1") (pin "2") (pinfunction "Emitter_2") (pintype "passive"))
    )
    (net (code "68") (name "Net-(VT2-Base)") (class "Default")
      (node (ref "R231") (pin "2") (pinfunction "2_2") (pintype "passive"))
      (node (ref "VT2") (pin "1") (pinfunction "Base_1") (pintype "passive"))
    )
    (net (code "69") (name "Net-(VT2-Collector)") (class "Default")
      (node (ref "R239") (pin "1") (pinfunction "1_1") (pintype "passive"))
      (node (ref "VT2") (pin "3") (pinfunction "Collector_3") (pintype "passive"))
    )
    (net (code "70") (name "Net-(VT3-Base)") (class "Default")
      (node (ref "R233") (pin "2") (pinfunction "2_2") (pintype "passive"))
      (node (ref "VT3") (pin "1") (pinfunction "Base_1") (pintype "passive"))
    )
    (net (code "71") (name "Net-(VT3-Collector)") (class "Default")
      (node (ref "R236") (pin "1") (pinfunction "1_1") (pintype "passive"))
      (node (ref "R237") (pin "1") (pinfunction "1_1") (pintype "passive"))
      (node (ref "VT3") (pin "3") (pinfunction "Collector_3") (pintype "passive"))
    )
    (net (code "72") (name "Net-(VT4-Base)") (class "Default")
      (node (ref "R232") (pin "2") (pinfunction "2_2") (pintype "passive"))
      (node (ref "VT4") (pin "1") (pinfunction "Base_1") (pintype "passive"))
    )
    (net (code "73") (name "Net-(VT4-Collector)") (class "Default")
      (node (ref "R238") (pin "1") (pinfunction "1_1") (pintype "passive"))
      (node (ref "VT4") (pin "3") (pinfunction "Collector_3") (pintype "passive"))
    )
    (net (code "74") (name "P3V3") (class "Default")
      (node (ref "R237") (pin "2") (pinfunction "2_2") (pintype "passive"))
    )
    (net (code "75") (name "unconnected-(DD14-1A-Pad2)") (class "Default")
      (node (ref "DD14") (pin "2") (pinfunction "1A_2") (pintype "passive"))
    )
    (net (code "76") (name "unconnected-(DD14-1OE_-Pad1)") (class "Default")
      (node (ref "DD14") (pin "1") (pinfunction "1OE__1") (pintype "passive"))
    )
    (net (code "77") (name "unconnected-(DD14-2A-Pad5)") (class "Default")
      (node (ref "DD14") (pin "5") (pinfunction "2A_5") (pintype "passive"))
    )
    (net (code "78") (name "unconnected-(DD14-2OE_-Pad4)") (class "Default")
      (node (ref "DD14") (pin "4") (pinfunction "2OE__4") (pintype "passive"))
    )
    (net (code "79") (name "unconnected-(DD14-2Y-Pad6)") (class "Default")
      (node (ref "DD14") (pin "6") (pinfunction "2Y_6") (pintype "passive"))
    )
    (net (code "80") (name "unconnected-(DD14-3A-Pad9)") (class "Default")
      (node (ref "DD14") (pin "9") (pinfunction "3A_9") (pintype "passive"))
    )
    (net (code "81") (name "unconnected-(DD14-3OE_-Pad10)") (class "Default")
      (node (ref "DD14") (pin "10") (pinfunction "3OE__10") (pintype "passive"))
    )
    (net (code "82") (name "unconnected-(DD14-3Y-Pad8)") (class "Default")
      (node (ref "DD14") (pin "8") (pinfunction "3Y_8") (pintype "passive"))
    )
  )
)
